# pluginboard_HP.net
KiCad netlist of a schematic drawn in EAGLE
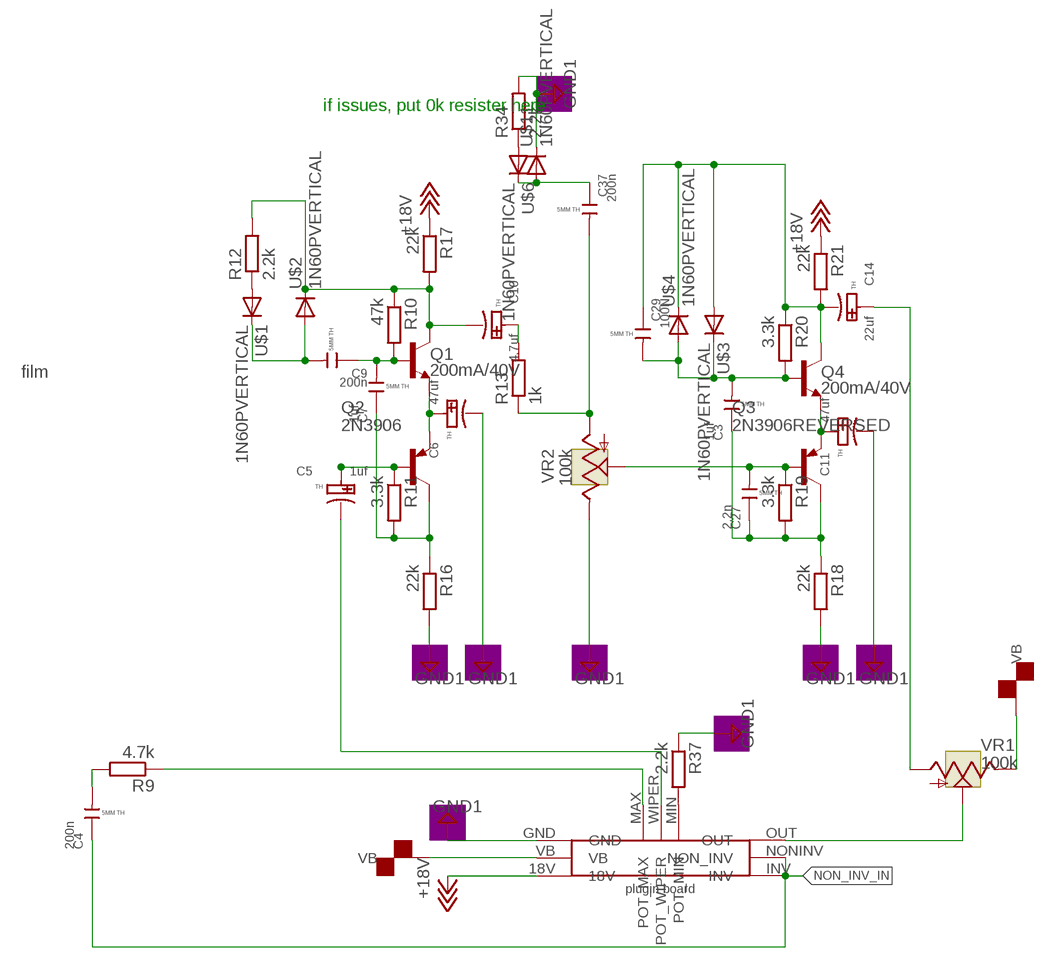
[diagram p0: schematic, sheet 1]

(export (version "E")
  (design (tool "Eeschema 10.0.6"))
  (components
    (comp (ref "C3")
      (value "1uf")
      (footprint "eagle-import:CERAMIC-5MM")
      (fields (field (name "PACKAGE") "5MM TH"))
      (libsource (lib "eagle-import") (part "THRU_HOLE_5MM_SPACING"))
    )
    (comp (ref "C4")
      (value "200n")
      (footprint "eagle-import:CERAMIC-5MM")
      (fields (field (name "PACKAGE") "5MM TH"))
      (libsource (lib "eagle-import") (part "THRU_HOLE_5MM_SPACING"))
    )
    (comp (ref "C5")
      (value "1uf")
      (footprint "eagle-import:PC-D5.3MM")
      (fields (field (name "PACKAGE") "TH"))
      (libsource (lib "eagle-import") (part "THRU-HOLE-POLARIZED"))
    )
    (comp (ref "C6")
      (value "47uf")
      (footprint "eagle-import:PC-D5.3MM")
      (fields (field (name "PACKAGE") "TH"))
      (libsource (lib "eagle-import") (part "THRU-HOLE-POLARIZED"))
    )
    (comp (ref "C7")
      (value "1uf")
      (footprint "eagle-import:CERAMIC-5MM")
      (fields (field (name "PACKAGE") "5MM TH"))
      (libsource (lib "eagle-import") (part "THRU_HOLE_5MM_SPACING"))
    )
    (comp (ref "C9")
      (value "200n")
      (footprint "eagle-import:CERAMIC-5MM")
      (fields (field (name "PACKAGE") "5MM TH"))
      (libsource (lib "eagle-import") (part "THRU_HOLE_5MM_SPACING"))
    )
    (comp (ref "C10")
      (value "4.7uf")
      (footprint "eagle-import:PC-D5.3MM")
      (fields (field (name "PACKAGE") "TH"))
      (libsource (lib "eagle-import") (part "THRU-HOLE-POLARIZED"))
    )
    (comp (ref "C11")
      (value "47uf")
      (footprint "eagle-import:PC-D5.3MM")
      (fields (field (name "PACKAGE") "TH"))
      (libsource (lib "eagle-import") (part "THRU-HOLE-POLARIZED"))
    )
    (comp (ref "C14")
      (value "22uf")
      (footprint "eagle-import:PC-D5.3MM")
      (fields (field (name "PACKAGE") "TH"))
      (libsource (lib "eagle-import") (part "THRU-HOLE-POLARIZED"))
    )
    (comp (ref "C27")
      (value "2.2n")
      (footprint "eagle-import:CERAMIC-5MM")
      (fields (field (name "PACKAGE") "5MM TH"))
      (libsource (lib "eagle-import") (part "THRU_HOLE_5MM_SPACING"))
    )
    (comp (ref "C29")
      (value "100N")
      (footprint "eagle-import:CERAMIC-5MM")
      (fields (field (name "PACKAGE") "5MM TH"))
      (libsource (lib "eagle-import") (part "THRU_HOLE_5MM_SPACING"))
    )
    (comp (ref "C37")
      (value "200n")
      (footprint "eagle-import:CERAMIC-5MM")
      (fields (field (name "PACKAGE") "5MM TH"))
      (libsource (lib "eagle-import") (part "THRU_HOLE_5MM_SPACING"))
    )
    (comp (ref "Q1")
      (value "200mA/40V")
      (footprint "eagle-import:TO-92")
      (libsource (lib "eagle-import") (part "TRANS_NPN-2N3904"))
    )
    (comp (ref "Q2")
      (value "2N3906")
      (footprint "eagle-import:TO92")
      (libsource (lib "eagle-import") (part "2N3906"))
    )
    (comp (ref "Q3")
      (value "2N3906REVERSED")
      (footprint "eagle-import:2N3906REVERSED")
      (libsource (lib "eagle-import") (part "2N3906REVERSED"))
    )
    (comp (ref "Q4")
      (value "200mA/40V")
      (footprint "eagle-import:TO-92")
      (libsource (lib "eagle-import") (part "TRANS_NPN-2N3904"))
    )
    (comp (ref "R9")
      (value "4.7k")
      (footprint "eagle-import:R1206")
      (libsource (lib "eagle-import") (part "R-EU_R1206"))
    )
    (comp (ref "R10")
      (value "47k")
      (footprint "eagle-import:R1206")
      (libsource (lib "eagle-import") (part "R-EU_R1206"))
    )
    (comp (ref "R11")
      (value "3.3k")
      (footprint "eagle-import:R1206")
      (libsource (lib "eagle-import") (part "R-EU_R1206"))
    )
    (comp (ref "R12")
      (value "2.2k")
      (footprint "eagle-import:R1206")
      (libsource (lib "eagle-import") (part "R-EU_R1206"))
    )
    (comp (ref "R13")
      (value "1k")
      (footprint "eagle-import:R1206")
      (libsource (lib "eagle-import") (part "R-EU_R1206"))
    )
    (comp (ref "R16")
      (value "22k")
      (footprint "eagle-import:R1206")
      (libsource (lib "eagle-import") (part "R-EU_R1206"))
    )
    (comp (ref "R17")
      (value "22k")
      (footprint "eagle-import:R1206")
      (libsource (lib "eagle-import") (part "R-EU_R1206"))
    )
    (comp (ref "R18")
      (value "22k")
      (footprint "eagle-import:R1206")
      (libsource (lib "eagle-import") (part "R-EU_R1206"))
    )
    (comp (ref "R19")
      (value "3.3k")
      (footprint "eagle-import:R1206")
      (libsource (lib "eagle-import") (part "R-EU_R1206"))
    )
    (comp (ref "R20")
      (value "3.3k")
      (footprint "eagle-import:R1206")
      (libsource (lib "eagle-import") (part "R-EU_R1206"))
    )
    (comp (ref "R21")
      (value "22k")
      (footprint "eagle-import:R1206")
      (libsource (lib "eagle-import") (part "R-EU_R1206"))
    )
    (comp (ref "R34")
      (value "2.2k")
      (footprint "eagle-import:R1206")
      (libsource (lib "eagle-import") (part "R-EU_R1206"))
    )
    (comp (ref "R37")
      (value "2.2k")
      (footprint "eagle-import:R1206")
      (libsource (lib "eagle-import") (part "R-EU_R1206"))
    )
    (comp (ref "U$1")
      (value "1N60PVERTICAL")
      (footprint "eagle-import:DO41-1")
      (libsource (lib "eagle-import") (part "1N60PVERTICAL"))
    )
    (comp (ref "U$2")
      (value "1N60PVERTICAL")
      (footprint "eagle-import:DO41-1")
      (libsource (lib "eagle-import") (part "1N60PVERTICAL"))
    )
    (comp (ref "U$3")
      (value "1N60PVERTICAL")
      (footprint "eagle-import:DO41-1")
      (libsource (lib "eagle-import") (part "1N60PVERTICAL"))
    )
    (comp (ref "U$4")
      (value "1N60PVERTICAL")
      (footprint "eagle-import:DO41-1")
      (libsource (lib "eagle-import") (part "1N60PVERTICAL"))
    )
    (comp (ref "U$6")
      (value "1N60PVERTICAL")
      (footprint "eagle-import:DO41-1")
      (libsource (lib "eagle-import") (part "1N60PVERTICAL"))
    )
    (comp (ref "U$9")
      (value "GT_BOARD")
      (footprint "eagle-import:PLUGIN_BOARD")
      (libsource (lib "eagle-import") (part "GT_BOARD"))
    )
    (comp (ref "U$11")
      (value "1N60PVERTICAL")
      (footprint "eagle-import:DO41-1")
      (libsource (lib "eagle-import") (part "1N60PVERTICAL"))
    )
    (comp (ref "VR1")
      (value "100k")
      (footprint "eagle-import:3223G")
      (libsource (lib "eagle-import") (part "TRIM_US-3223G"))
    )
    (comp (ref "VR2")
      (value "100k")
      (footprint "eagle-import:3223G")
      (libsource (lib "eagle-import") (part "TRIM_US-3223G"))
    )
  )
  (nets
    (net (code "1") (name "+18V") (class "Default")
      (node (ref "R17") (pin "1") (pinfunction "1_1") (pintype "passive"))
      (node (ref "R21") (pin "1") (pinfunction "1_1") (pintype "passive"))
      (node (ref "U$9") (pin "18V") (pinfunction "18V_18V") (pintype "bidirectional"))
    )
    (net (code "2") (name "GND1") (class "Default")
      (node (ref "C11") (pin "-") (pinfunction "-_-") (pintype "passive"))
      (node (ref "C6") (pin "-") (pinfunction "-_-") (pintype "passive"))
      (node (ref "R16") (pin "2") (pinfunction "2_2") (pintype "passive"))
      (node (ref "R18") (pin "2") (pinfunction "2_2") (pintype "passive"))
      (node (ref "R34") (pin "2") (pinfunction "2_2") (pintype "passive"))
      (node (ref "R37") (pin "1") (pinfunction "1_1") (pintype "passive"))
      (node (ref "U$11") (pin "C") (pinfunction "C_C") (pintype "passive"))
      (node (ref "U$9") (pin "GND") (pinfunction "GND_GND") (pintype "bidirectional"))
      (node (ref "VR2") (pin "3") (pinfunction "E_3") (pintype "passive"))
    )
    (net (code "3") (name "NON_INV_IN") (class "Default")
      (node (ref "C4") (pin "1") (pinfunction "1_1") (pintype "passive"))
      (node (ref "U$9") (pin "INV") (pinfunction "INV_INV") (pintype "bidirectional"))
      (node (ref "U$9") (pin "NONINV") (pinfunction "NON_INV_NONINV") (pintype "bidirectional"))
    )
    (net (code "4") (name "Net-(C4-Pad2)") (class "Default")
      (node (ref "C4") (pin "2") (pinfunction "2_2") (pintype "passive"))
      (node (ref "R9") (pin "2") (pinfunction "2_2") (pintype "passive"))
    )
    (net (code "5") (name "Net-(C9-Pad2)") (class "Default")
      (node (ref "C9") (pin "2") (pinfunction "2_2") (pintype "passive"))
      (node (ref "U$1") (pin "C") (pinfunction "C_C") (pintype "passive"))
      (node (ref "U$2") (pin "A") (pinfunction "A_A") (pintype "passive"))
    )
    (net (code "6") (name "Net-(C10-Pad+)") (class "Default")
      (node (ref "C10") (pin "+") (pinfunction "+_+") (pintype "passive"))
      (node (ref "R13") (pin "2") (pinfunction "2_2") (pintype "passive"))
    )
    (net (code "7") (name "Net-(C37-Pad1)") (class "Default")
      (node (ref "C37") (pin "1") (pinfunction "1_1") (pintype "passive"))
      (node (ref "U$11") (pin "A") (pinfunction "A_A") (pintype "passive"))
      (node (ref "U$6") (pin "C") (pinfunction "C_C") (pintype "passive"))
    )
    (net (code "8") (name "Net-(Q1-B)") (class "Default")
      (node (ref "C7") (pin "2") (pinfunction "2_2") (pintype "passive"))
      (node (ref "C9") (pin "1") (pinfunction "1_1") (pintype "passive"))
      (node (ref "Q1") (pin "2") (pinfunction "B_2") (pintype "passive"))
      (node (ref "R10") (pin "2") (pinfunction "2_2") (pintype "passive"))
    )
    (net (code "9") (name "Net-(Q1-C)") (class "Default")
      (node (ref "C10") (pin "-") (pinfunction "-_-") (pintype "passive"))
      (node (ref "Q1") (pin "3") (pinfunction "C_3") (pintype "passive"))
      (node (ref "R10") (pin "1") (pinfunction "1_1") (pintype "passive"))
      (node (ref "R12") (pin "2") (pinfunction "2_2") (pintype "passive"))
      (node (ref "R17") (pin "2") (pinfunction "2_2") (pintype "passive"))
      (node (ref "U$2") (pin "C") (pinfunction "C_C") (pintype "passive"))
    )
    (net (code "10") (name "Net-(Q1-E)") (class "Default")
      (node (ref "C6") (pin "+") (pinfunction "+_+") (pintype "passive"))
      (node (ref "Q1") (pin "1") (pinfunction "E_1") (pintype "passive"))
      (node (ref "Q2") (pin "3") (pinfunction "E_3") (pintype "passive"))
    )
    (net (code "11") (name "Net-(Q2-B)") (class "Default")
      (node (ref "C5") (pin "+") (pinfunction "+_+") (pintype "passive"))
      (node (ref "Q2") (pin "2") (pinfunction "B_2") (pintype "passive"))
      (node (ref "R11") (pin "1") (pinfunction "1_1") (pintype "passive"))
    )
    (net (code "12") (name "Net-(Q2-C)") (class "Default")
      (node (ref "C7") (pin "1") (pinfunction "1_1") (pintype "passive"))
      (node (ref "Q2") (pin "1") (pinfunction "C_1") (pintype "passive"))
      (node (ref "R11") (pin "2") (pinfunction "2_2") (pintype "passive"))
      (node (ref "R16") (pin "1") (pinfunction "1_1") (pintype "passive"))
    )
    (net (code "13") (name "Net-(Q3-B)") (class "Default")
      (node (ref "C27") (pin "2") (pinfunction "2_2") (pintype "passive"))
      (node (ref "Q3") (pin "2") (pinfunction "B_2") (pintype "passive"))
      (node (ref "R19") (pin "1") (pinfunction "1_1") (pintype "passive"))
      (node (ref "VR2") (pin "2") (pinfunction "S_2") (pintype "passive"))
    )
    (net (code "14") (name "Net-(Q3-C)") (class "Default")
      (node (ref "C27") (pin "1") (pinfunction "1_1") (pintype "passive"))
      (node (ref "C3") (pin "1") (pinfunction "1_1") (pintype "passive"))
      (node (ref "Q3") (pin "1") (pinfunction "C_1") (pintype "passive"))
      (node (ref "R18") (pin "1") (pinfunction "1_1") (pintype "passive"))
      (node (ref "R19") (pin "2") (pinfunction "2_2") (pintype "passive"))
    )
    (net (code "15") (name "Net-(Q3-E)") (class "Default")
      (node (ref "C11") (pin "+") (pinfunction "+_+") (pintype "passive"))
      (node (ref "Q3") (pin "3") (pinfunction "E_3") (pintype "passive"))
      (node (ref "Q4") (pin "1") (pinfunction "E_1") (pintype "passive"))
    )
    (net (code "16") (name "Net-(Q4-B)") (class "Default")
      (node (ref "C29") (pin "2") (pinfunction "2_2") (pintype "passive"))
      (node (ref "C3") (pin "2") (pinfunction "2_2") (pintype "passive"))
      (node (ref "Q4") (pin "2") (pinfunction "B_2") (pintype "passive"))
      (node (ref "R20") (pin "2") (pinfunction "2_2") (pintype "passive"))
      (node (ref "U$3") (pin "C") (pinfunction "C_C") (pintype "passive"))
      (node (ref "U$4") (pin "A") (pinfunction "A_A") (pintype "passive"))
    )
    (net (code "17") (name "Net-(Q4-C)") (class "Default")
      (node (ref "C14") (pin "-") (pinfunction "-_-") (pintype "passive"))
      (node (ref "C29") (pin "1") (pinfunction "1_1") (pintype "passive"))
      (node (ref "Q4") (pin "3") (pinfunction "C_3") (pintype "passive"))
      (node (ref "R20") (pin "1") (pinfunction "1_1") (pintype "passive"))
      (node (ref "R21") (pin "2") (pinfunction "2_2") (pintype "passive"))
      (node (ref "U$3") (pin "A") (pinfunction "A_A") (pintype "passive"))
      (node (ref "U$4") (pin "C") (pinfunction "C_C") (pintype "passive"))
    )
    (net (code "18") (name "Net-(R12-Pad1)") (class "Default")
      (node (ref "R12") (pin "1") (pinfunction "1_1") (pintype "passive"))
      (node (ref "U$1") (pin "A") (pinfunction "A_A") (pintype "passive"))
    )
    (net (code "19") (name "Net-(R34-Pad1)") (class "Default")
      (node (ref "R34") (pin "1") (pinfunction "1_1") (pintype "passive"))
      (node (ref "U$6") (pin "A") (pinfunction "A_A") (pintype "passive"))
    )
    (net (code "20") (name "Net-(U$9-POT_MAX)") (class "Default")
      (node (ref "R9") (pin "1") (pinfunction "1_1") (pintype "passive"))
      (node (ref "U$9") (pin "MAX") (pinfunction "POT_MAX_MAX") (pintype "bidirectional"))
    )
    (net (code "21") (name "Net-(U$9-POT_MIN)") (class "Default")
      (node (ref "R37") (pin "2") (pinfunction "2_2") (pintype "passive"))
      (node (ref "U$9") (pin "MIN") (pinfunction "POT_MIN_MIN") (pintype "bidirectional"))
    )
    (net (code "22") (name "Net-(U$9-POT_WIPER)") (class "Default")
      (node (ref "C5") (pin "-") (pinfunction "-_-") (pintype "passive"))
      (node (ref "U$9") (pin "WIPER") (pinfunction "POT_WIPER_WIPER") (pintype "bidirectional"))
    )
    (net (code "23") (name "Net-(VR1-A)") (class "Default")
      (node (ref "C14") (pin "+") (pinfunction "+_+") (pintype "passive"))
      (node (ref "VR1") (pin "1") (pinfunction "A_1") (pintype "passive"))
    )
    (net (code "24") (name "Net-(VR1-S)") (class "Default")
      (node (ref "U$9") (pin "OUT") (pinfunction "OUT_OUT") (pintype "bidirectional"))
      (node (ref "VR1") (pin "2") (pinfunction "S_2") (pintype "passive"))
    )
    (net (code "25") (name "Net-(VR2-A)") (class "Default")
      (node (ref "C37") (pin "2") (pinfunction "2_2") (pintype "passive"))
      (node (ref "R13") (pin "1") (pinfunction "1_1") (pintype "passive"))
      (node (ref "VR2") (pin "1") (pinfunction "A_1") (pintype "passive"))
    )
    (net (code "26") (name "VB") (class "Default")
      (node (ref "U$9") (pin "VB") (pinfunction "VB_VB") (pintype "bidirectional"))
      (node (ref "VR1") (pin "3") (pinfunction "E_3") (pintype "passive"))
    )
  )
)
